# MercurialSDR_FPGA_P_P.net
KiCad netlist of a schematic drawn in Altium Designer
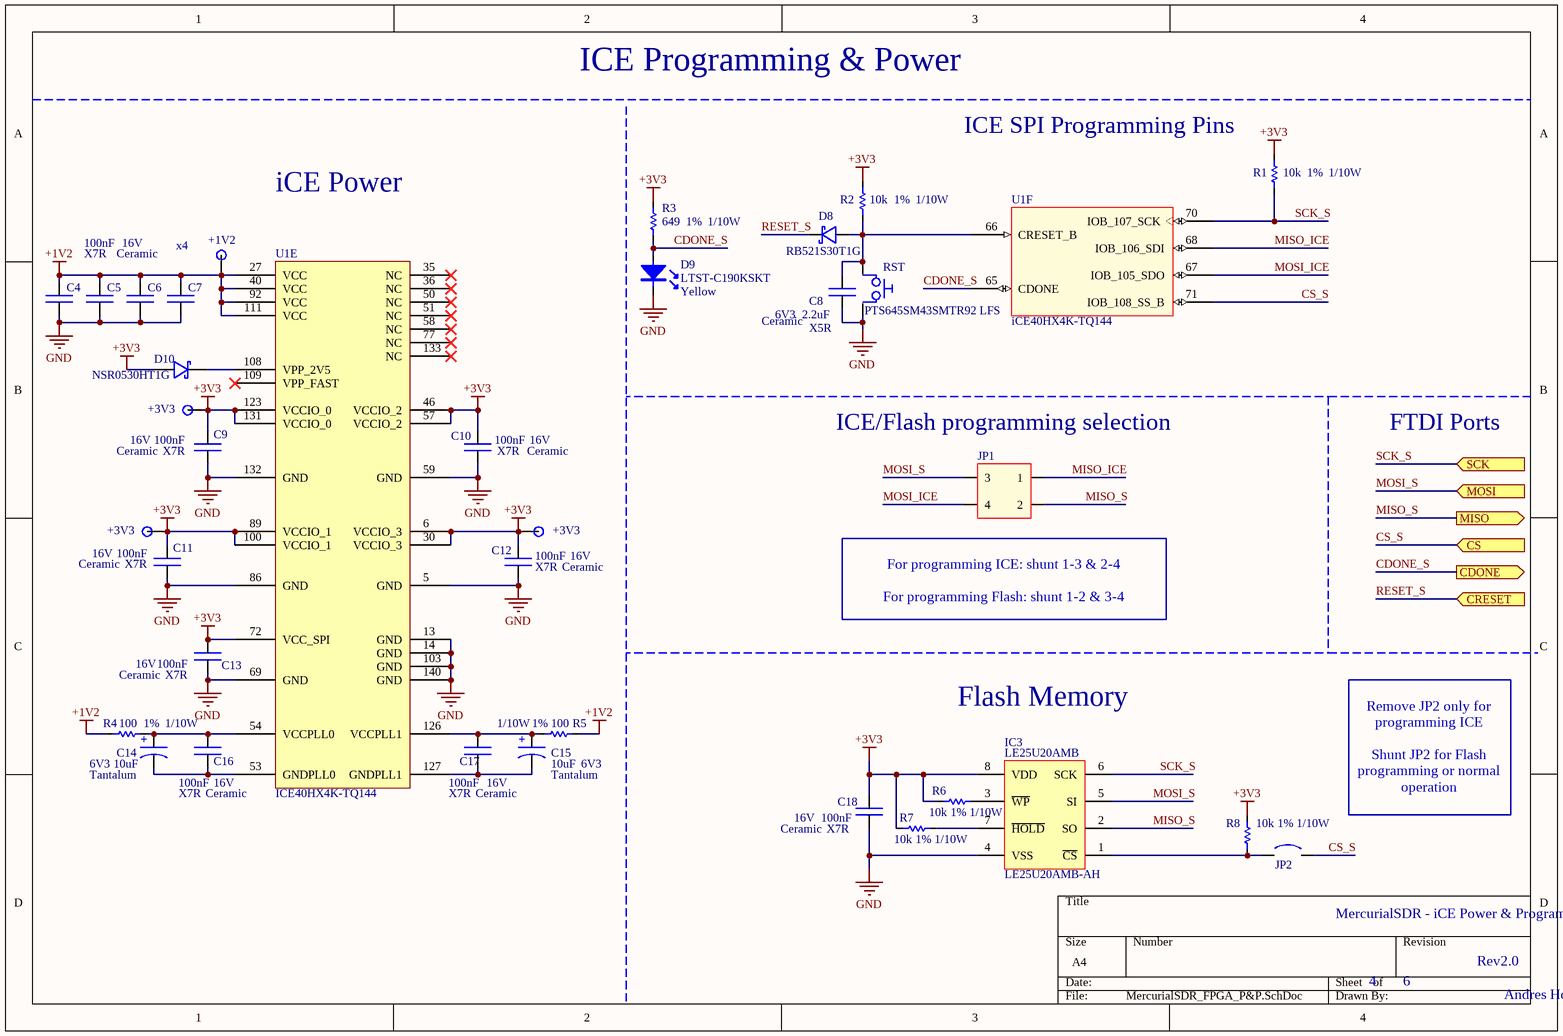
[diagram p0: MercurialSDR_FPGA_P&P.SchDoc]

(export (version "E")
  (design (tool "Eeschema 10.0.6"))
  (components
    (comp (ref "C4")
      (value "Capacitor")
      (footprint "CAP_0603")
      (description "Capacitor no polarizado")
      (fields (field (name "PART NUMBER") "CL10B104KO8NNNC"))
      (libsource (lib "MercurialSDR") (part "Cap"))
    )
    (comp (ref "C5")
      (value "Capacitor")
      (footprint "CAP_0603")
      (description "Capacitor no polarizado")
      (fields (field (name "PART NUMBER") "CL10B104KO8NNNC"))
      (libsource (lib "MercurialSDR") (part "Cap"))
    )
    (comp (ref "C6")
      (value "Capacitor")
      (footprint "CAP_0603")
      (description "Capacitor no polarizado")
      (fields (field (name "PART NUMBER") "CL10B104KO8NNNC"))
      (libsource (lib "MercurialSDR") (part "Cap"))
    )
    (comp (ref "C7")
      (value "100nF")
      (footprint "CAP_0603")
      (description "Capacitor no polarizado")
      (fields
        (field (name "TEMP COEF") "X7R")
        (field (name "PART NUMBER") "CL10B104KO8NNNC")
        (field (name "VR") "16V")
        (field (name "MATERIAL") "Ceramic")
        (field (name "Comment") "Capacitor")
      )
      (libsource (lib "MercurialSDR") (part "Cap"))
    )
    (comp (ref "C8")
      (value "2.2uF")
      (footprint "CAP_0603")
      (description "Capacitor no polarizado")
      (fields
        (field (name "TEMP COEF") "X5R")
        (field (name "PART NUMBER") "CL10A225KQ8NNNC")
        (field (name "VR") "6V3")
        (field (name "MATERIAL") "Ceramic")
        (field (name "Comment") "Capacitor")
      )
      (libsource (lib "MercurialSDR") (part "Cap"))
    )
    (comp (ref "C9")
      (value "100nF")
      (footprint "CAP_0603")
      (description "Capacitor no polarizado")
      (fields
        (field (name "TEMP COEF") "X7R")
        (field (name "PART NUMBER") "CL10B104KO8NNNC")
        (field (name "VR") "16V")
        (field (name "MATERIAL") "Ceramic")
        (field (name "Comment") "Capacitor")
      )
      (libsource (lib "MercurialSDR") (part "Cap"))
    )
    (comp (ref "C10")
      (value "100nF")
      (footprint "CAP_0603")
      (description "Capacitor no polarizado")
      (fields
        (field (name "TEMP COEF") "X7R")
        (field (name "PART NUMBER") "CL10B104KO8NNNC")
        (field (name "VR") "16V")
        (field (name "MATERIAL") "Ceramic")
        (field (name "Comment") "Capacitor")
      )
      (libsource (lib "MercurialSDR") (part "Cap"))
    )
    (comp (ref "C11")
      (value "100nF")
      (footprint "CAP_0603")
      (description "Capacitor no polarizado")
      (fields
        (field (name "TEMP COEF") "X7R")
        (field (name "PART NUMBER") "CL10B104KO8NNNC")
        (field (name "VR") "16V")
        (field (name "MATERIAL") "Ceramic")
        (field (name "Comment") "Capacitor")
      )
      (libsource (lib "MercurialSDR") (part "Cap"))
    )
    (comp (ref "C12")
      (value "100nF")
      (footprint "CAP_0603")
      (description "Capacitor no polarizado")
      (fields
        (field (name "TEMP COEF") "X7R")
        (field (name "PART NUMBER") "CL10B104KO8NNNC")
        (field (name "VR") "16V")
        (field (name "MATERIAL") "Ceramic")
        (field (name "Comment") "Capacitor")
      )
      (libsource (lib "MercurialSDR") (part "Cap"))
    )
    (comp (ref "C13")
      (value "100nF")
      (footprint "CAP_0603")
      (description "Capacitor no polarizado")
      (fields
        (field (name "TEMP COEF") "X7R")
        (field (name "PART NUMBER") "CL10B104KO8NNNC")
        (field (name "VR") "16V")
        (field (name "MATERIAL") "Ceramic")
        (field (name "Comment") "Capacitor")
      )
      (libsource (lib "MercurialSDR") (part "Cap"))
    )
    (comp (ref "C14")
      (value "10uF")
      (footprint "CAP_TANT_1206")
      (description "Capacitor polarizado")
      (fields
        (field (name "PART NUMBER") "TAJA106K006RNJ")
        (field (name "VR") "6V3")
        (field (name "MATERIAL") "Tantalum")
        (field (name "Comment") "Capacitor Polarizado")
      )
      (libsource (lib "MercurialSDR") (part "Cap Pol"))
    )
    (comp (ref "C15")
      (value "10uF")
      (footprint "CAP_TANT_1206")
      (description "Capacitor polarizado")
      (fields
        (field (name "PART NUMBER") "TAJA106K006RNJ")
        (field (name "VR") "6V3")
        (field (name "MATERIAL") "Tantalum")
        (field (name "Comment") "Capacitor Polarizado")
      )
      (libsource (lib "MercurialSDR") (part "Cap Pol"))
    )
    (comp (ref "C16")
      (value "100nF")
      (footprint "CAP_0603")
      (description "Capacitor no polarizado")
      (fields
        (field (name "TEMP COEF") "X7R")
        (field (name "PART NUMBER") "CL10B104KO8NNNC")
        (field (name "VR") "16V")
        (field (name "MATERIAL") "Ceramic")
        (field (name "Comment") "Capacitor")
      )
      (libsource (lib "MercurialSDR") (part "Cap"))
    )
    (comp (ref "C17")
      (value "100nF")
      (footprint "CAP_0603")
      (description "Capacitor no polarizado")
      (fields
        (field (name "TEMP COEF") "X7R")
        (field (name "PART NUMBER") "CL10B104KO8NNNC")
        (field (name "VR") "16V")
        (field (name "MATERIAL") "Ceramic")
        (field (name "Comment") "Capacitor")
      )
      (libsource (lib "MercurialSDR") (part "Cap"))
    )
    (comp (ref "C18")
      (value "100nF")
      (footprint "CAP_0603")
      (description "Capacitor no polarizado")
      (fields
        (field (name "TEMP COEF") "X7R")
        (field (name "PART NUMBER") "CL10B104KO8NNNC")
        (field (name "VR") "16V")
        (field (name "MATERIAL") "Ceramic")
        (field (name "Comment") "Capacitor")
      )
      (libsource (lib "MercurialSDR") (part "Cap"))
    )
    (comp (ref "D8")
      (value "Schottky Diode")
      (footprint "SOD-523")
      (description "Diodo Schottkey")
      (fields (field (name "PART NUMBER") "RB521S30T1G"))
      (libsource (lib "MercurialSDR") (part "Diodo_Schottky"))
    )
    (comp (ref "D9")
      (value "Led")
      (footprint "LED_0603")
      (fields (field (name "COLOR") "Yellow") (field (name "PART NUMBER") "LTST-C190KSKT"))
      (libsource (lib "MercurialSDR") (part "Led"))
    )
    (comp (ref "D10")
      (value "Schottky Diode")
      (footprint "SOD-323")
      (description "Diodo Schottkey")
      (fields (field (name "PART NUMBER") "NSR0530HT1G"))
      (libsource (lib "") (part "Diodo_Schottky_1"))
    )
    (comp (ref "IC3")
      (value "LE25U20AMB")
      (footprint "SOIC-8")
      (description "Flash Memmory SPI (256Kx8)")
      (fields (field (name "PART NUMBER") "LE25U20AMB-AH"))
      (libsource (lib "MercurialSDR") (part "LE25U20AMB"))
    )
    (comp (ref "JP1")
      (value "Jumper")
      (footprint "Jumper 2x2")
      (description "Jumper 2x2")
      (libsource (lib "MercurialSDR") (part "Jumper 2x2"))
    )
    (comp (ref "JP2")
      (value "Jumper")
      (footprint "Jumper 2x1")
      (libsource (lib "MercurialSDR") (part "Jumper"))
    )
    (comp (ref "R1")
      (value "10k")
      (footprint "RES_0603")
      (description "Resistor")
      (fields
        (field (name "POWER") "1/10W")
        (field (name "PART NUMBER") "CR0603-FX-1002EAS")
        (field (name "TOLERANCE") "1%")
        (field (name "Comment") "Resistor SMD")
      )
      (libsource (lib "MercurialSDR") (part "Res"))
    )
    (comp (ref "R2")
      (value "10k")
      (footprint "RES_0603")
      (description "Resistor")
      (fields
        (field (name "POWER") "1/10W")
        (field (name "PART NUMBER") "CR0603-FX-1002EAS")
        (field (name "TOLERANCE") "1%")
        (field (name "Comment") "Resistor SMD")
      )
      (libsource (lib "MercurialSDR") (part "Res"))
    )
    (comp (ref "R3")
      (value "649")
      (footprint "RES_0603")
      (description "Resistor")
      (fields
        (field (name "POWER") "1/10W")
        (field (name "PART NUMBER") "RC0603FR-07649RL")
        (field (name "TOLERANCE") "1%")
        (field (name "Comment") "Resistor SMD")
      )
      (libsource (lib "MercurialSDR") (part "Res"))
    )
    (comp (ref "R4")
      (value "100")
      (footprint "RES_0603")
      (description "Resistor")
      (fields
        (field (name "POWER") "1/10W")
        (field (name "PART NUMBER") "CR0603-FX-1000ELF")
        (field (name "TOLERANCE") "1%")
        (field (name "Comment") "Resistor SMD")
      )
      (libsource (lib "MercurialSDR") (part "Res"))
    )
    (comp (ref "R5")
      (value "100")
      (footprint "RES_0603")
      (description "Resistor")
      (fields
        (field (name "POWER") "1/10W")
        (field (name "PART NUMBER") "CR0603-FX-1000ELF")
        (field (name "TOLERANCE") "1%")
        (field (name "Comment") "Resistor SMD")
      )
      (libsource (lib "MercurialSDR") (part "Res"))
    )
    (comp (ref "R6")
      (value "10k")
      (footprint "RES_0603")
      (description "Resistor")
      (fields
        (field (name "POWER") "1/10W")
        (field (name "PART NUMBER") "CR0603-FX-1002EAS")
        (field (name "TOLERANCE") "1%")
        (field (name "Comment") "Resistor SMD")
      )
      (libsource (lib "MercurialSDR") (part "Res"))
    )
    (comp (ref "R7")
      (value "10k")
      (footprint "RES_0603")
      (description "Resistor")
      (fields
        (field (name "POWER") "1/10W")
        (field (name "PART NUMBER") "CR0603-FX-1002EAS")
        (field (name "TOLERANCE") "1%")
        (field (name "Comment") "Resistor SMD")
      )
      (libsource (lib "MercurialSDR") (part "Res"))
    )
    (comp (ref "R8")
      (value "10k")
      (footprint "RES_0603")
      (description "Resistor")
      (fields
        (field (name "POWER") "1/10W")
        (field (name "PART NUMBER") "CR0603-FX-1002EAS")
        (field (name "TOLERANCE") "1%")
        (field (name "Comment") "Resistor SMD")
      )
      (libsource (lib "MercurialSDR") (part "Res"))
    )
    (comp (ref "SW4")
      (value "Pulsador")
      (footprint "SWITCH_6X6mm")
      (fields (field (name "PART NUMBER") "PTS645SM43SMTR92 LFS") (field (name "SERIGRAFIA") "RST"))
      (libsource (lib "MercurialSDR") (part "Pulsador"))
    )
    (comp (ref "TP3")
      (value "Test Point")
      (footprint "TP_TOP")
      (fields (field (name "TP NAME") "+1V2"))
      (libsource (lib "MercurialSDR") (part "Test Point"))
    )
    (comp (ref "TP4")
      (value "Test Point")
      (footprint "TP_TOP")
      (fields (field (name "TP NAME") "+3V3"))
      (libsource (lib "MercurialSDR") (part "Test Point"))
    )
    (comp (ref "TP6")
      (value "Test Point")
      (footprint "TP_TOP")
      (fields (field (name "TP NAME") "+3V3"))
      (libsource (lib "MercurialSDR") (part "Test Point"))
    )
    (comp (ref "TP7")
      (value "Test Point")
      (footprint "TP_TOP")
      (fields (field (name "TP NAME") "+3V3"))
      (libsource (lib "MercurialSDR") (part "Test Point"))
    )
    (comp (ref "U1")
      (value "ICE40HX4K-TQ144")
      (footprint "LATC-TQFP-144_L")
      (fields
        (field (name "MANUFACTURER") "Lattice Semiconductor")
        (field (name "PARTNUMBER") "ICE40HX4K-TQ144")
      )
      (libsource (lib "MercurialSDR") (part "ICE40HX4K-TQ144"))
    )
  )
  (nets
    (net (code "1") (name "+1V2") (class "Default")
      (node (ref "C4") (pin "1") (pinfunction "1_1") (pintype "passive"))
      (node (ref "C5") (pin "1") (pinfunction "1_1") (pintype "passive"))
      (node (ref "C6") (pin "1") (pinfunction "1_1") (pintype "passive"))
      (node (ref "C7") (pin "1") (pinfunction "1_1") (pintype "passive"))
      (node (ref "R4") (pin "2") (pinfunction "2_2") (pintype "passive"))
      (node (ref "R5") (pin "1") (pinfunction "1_1") (pintype "passive"))
      (node (ref "TP3") (pin "1") (pinfunction "TP?_1") (pintype "passive"))
      (node (ref "U1") (pin "111") (pinfunction "VCC_111") (pintype "power_in"))
      (node (ref "U1") (pin "27") (pinfunction "VCC_27") (pintype "power_in"))
      (node (ref "U1") (pin "40") (pinfunction "VCC_40") (pintype "power_in"))
      (node (ref "U1") (pin "92") (pinfunction "VCC_92") (pintype "power_in"))
    )
    (net (code "2") (name "+3V3") (class "Default")
      (node (ref "C10") (pin "2") (pinfunction "2_2") (pintype "passive"))
      (node (ref "C11") (pin "2") (pinfunction "2_2") (pintype "passive"))
      (node (ref "C12") (pin "2") (pinfunction "2_2") (pintype "passive"))
      (node (ref "C13") (pin "2") (pinfunction "2_2") (pintype "passive"))
      (node (ref "C18") (pin "2") (pinfunction "2_2") (pintype "passive"))
      (node (ref "C9") (pin "2") (pinfunction "2_2") (pintype "passive"))
      (node (ref "D10") (pin "1") (pinfunction "A_1") (pintype "passive"))
      (node (ref "IC3") (pin "8") (pinfunction "VDD_8") (pintype "passive"))
      (node (ref "R1") (pin "1") (pinfunction "1_1") (pintype "passive"))
      (node (ref "R2") (pin "1") (pinfunction "1_1") (pintype "passive"))
      (node (ref "R3") (pin "1") (pinfunction "1_1") (pintype "passive"))
      (node (ref "R6") (pin "1") (pinfunction "1_1") (pintype "passive"))
      (node (ref "R7") (pin "1") (pinfunction "1_1") (pintype "passive"))
      (node (ref "R8") (pin "2") (pinfunction "2_2") (pintype "passive"))
      (node (ref "TP4") (pin "1") (pinfunction "TP?_1") (pintype "passive"))
      (node (ref "TP6") (pin "1") (pinfunction "TP?_1") (pintype "passive"))
      (node (ref "TP7") (pin "1") (pinfunction "TP?_1") (pintype "passive"))
      (node (ref "U1") (pin "100") (pinfunction "VCCIO_1_100") (pintype "power_in"))
      (node (ref "U1") (pin "123") (pinfunction "VCCIO_0_123") (pintype "power_in"))
      (node (ref "U1") (pin "131") (pinfunction "VCCIO_0_131") (pintype "power_in"))
      (node (ref "U1") (pin "30") (pinfunction "VCCIO_3_30") (pintype "power_in"))
      (node (ref "U1") (pin "46") (pinfunction "VCCIO_2_46") (pintype "power_in"))
      (node (ref "U1") (pin "57") (pinfunction "VCCIO_2_57") (pintype "power_in"))
      (node (ref "U1") (pin "6") (pinfunction "VCCIO_3_6") (pintype "power_in"))
      (node (ref "U1") (pin "72") (pinfunction "VCC_SPI_72") (pintype "power_in"))
      (node (ref "U1") (pin "89") (pinfunction "VCCIO_1_89") (pintype "power_in"))
    )
    (net (code "3") (name "/CDONE_S") (class "Default")
      (node (ref "D9") (pin "1") (pinfunction "A_1") (pintype "passive"))
      (node (ref "R3") (pin "2") (pinfunction "2_2") (pintype "passive"))
      (node (ref "U1") (pin "65") (pinfunction "CDONE_65") (pintype "bidirectional"))
    )
    (net (code "4") (name "/CS_S") (class "Default")
      (node (ref "JP2") (pin "2") (pinfunction "2_2") (pintype "passive"))
      (node (ref "U1") (pin "71") (pinfunction "IOB_108_SS_B_71") (pintype "bidirectional"))
    )
    (net (code "5") (name "/MISO_ICE") (class "Default")
      (node (ref "JP1") (pin "1") (pinfunction "1_1") (pintype "passive"))
      (node (ref "U1") (pin "68") (pinfunction "IOB_106_SDI_68") (pintype "bidirectional"))
    )
    (net (code "6") (name "/MISO_S") (class "Default")
      (node (ref "IC3") (pin "2") (pinfunction "SO_2") (pintype "passive"))
      (node (ref "JP1") (pin "2") (pinfunction "2_2") (pintype "passive"))
    )
    (net (code "7") (name "/MOSI_ICE") (class "Default")
      (node (ref "JP1") (pin "4") (pinfunction "4_4") (pintype "passive"))
      (node (ref "U1") (pin "67") (pinfunction "IOB_105_SDO_67") (pintype "bidirectional"))
    )
    (net (code "8") (name "/MOSI_S") (class "Default")
      (node (ref "IC3") (pin "5") (pinfunction "SI_5") (pintype "passive"))
      (node (ref "JP1") (pin "3") (pinfunction "3_3") (pintype "passive"))
    )
    (net (code "9") (name "/RESET_S") (class "Default")
      (node (ref "D8") (pin "2") (pinfunction "K_2") (pintype "passive"))
    )
    (net (code "10") (name "/SCK_S") (class "Default")
      (node (ref "IC3") (pin "6") (pinfunction "SCK_6") (pintype "passive"))
      (node (ref "R1") (pin "2") (pinfunction "2_2") (pintype "passive"))
      (node (ref "U1") (pin "70") (pinfunction "IOB_107_SCK_70") (pintype "bidirectional"))
    )
    (net (code "11") (name "GND") (class "Default")
      (node (ref "C10") (pin "1") (pinfunction "1_1") (pintype "passive"))
      (node (ref "C11") (pin "1") (pinfunction "1_1") (pintype "passive"))
      (node (ref "C12") (pin "1") (pinfunction "1_1") (pintype "passive"))
      (node (ref "C13") (pin "1") (pinfunction "1_1") (pintype "passive"))
      (node (ref "C18") (pin "1") (pinfunction "1_1") (pintype "passive"))
      (node (ref "C4") (pin "2") (pinfunction "2_2") (pintype "passive"))
      (node (ref "C5") (pin "2") (pinfunction "2_2") (pintype "passive"))
      (node (ref "C6") (pin "2") (pinfunction "2_2") (pintype "passive"))
      (node (ref "C7") (pin "2") (pinfunction "2_2") (pintype "passive"))
      (node (ref "C8") (pin "2") (pinfunction "2_2") (pintype "passive"))
      (node (ref "C9") (pin "1") (pinfunction "1_1") (pintype "passive"))
      (node (ref "D9") (pin "2") (pinfunction "K_2") (pintype "passive"))
      (node (ref "IC3") (pin "4") (pinfunction "VSS_4") (pintype "passive"))
      (node (ref "SW4") (pin "4") (pinfunction "4_4") (pintype "passive"))
      (node (ref "U1") (pin "103") (pinfunction "GND_103") (pintype "power_in"))
      (node (ref "U1") (pin "13") (pinfunction "GND_13") (pintype "power_in"))
      (node (ref "U1") (pin "132") (pinfunction "GND_132") (pintype "power_in"))
      (node (ref "U1") (pin "14") (pinfunction "GND_14") (pintype "power_in"))
      (node (ref "U1") (pin "140") (pinfunction "GND_140") (pintype "power_in"))
      (node (ref "U1") (pin "5") (pinfunction "GND_5") (pintype "power_in"))
      (node (ref "U1") (pin "59") (pinfunction "GND_59") (pintype "power_in"))
      (node (ref "U1") (pin "69") (pinfunction "GND_69") (pintype "power_in"))
      (node (ref "U1") (pin "86") (pinfunction "GND_86") (pintype "power_in"))
    )
    (net (code "12") (name "Net-(D8-A)") (class "Default")
      (node (ref "C8") (pin "1") (pinfunction "1_1") (pintype "passive"))
      (node (ref "D8") (pin "1") (pinfunction "A_1") (pintype "passive"))
      (node (ref "R2") (pin "2") (pinfunction "2_2") (pintype "passive"))
      (node (ref "SW4") (pin "1") (pinfunction "1_1") (pintype "passive"))
      (node (ref "U1") (pin "66") (pinfunction "CRESET_B_66") (pintype "input"))
    )
    (net (code "13") (name "Net-(D10-K)") (class "Default")
      (node (ref "D10") (pin "2") (pinfunction "K_2") (pintype "passive"))
      (node (ref "U1") (pin "108") (pinfunction "VPP_2V5_108") (pintype "power_in"))
    )
    (net (code "14") (name "Net-(IC3-~{CS})") (class "Default")
      (node (ref "IC3") (pin "1") (pinfunction "~{CS}_1") (pintype "passive"))
      (node (ref "JP2") (pin "1") (pinfunction "1_1") (pintype "passive"))
      (node (ref "R8") (pin "1") (pinfunction "1_1") (pintype "passive"))
    )
    (net (code "15") (name "Net-(IC3-~{HOLD})") (class "Default")
      (node (ref "IC3") (pin "7") (pinfunction "~{HOLD}_7") (pintype "passive"))
      (node (ref "R7") (pin "2") (pinfunction "2_2") (pintype "passive"))
    )
    (net (code "16") (name "Net-(IC3-~{WP})") (class "Default")
      (node (ref "IC3") (pin "3") (pinfunction "~{WP}_3") (pintype "passive"))
      (node (ref "R6") (pin "2") (pinfunction "2_2") (pintype "passive"))
    )
    (net (code "17") (name "Net-(U1E-GNDPLL0)") (class "Default")
      (node (ref "C14") (pin "2") (pinfunction "2_2") (pintype "passive"))
      (node (ref "C16") (pin "2") (pinfunction "2_2") (pintype "passive"))
      (node (ref "U1") (pin "53") (pinfunction "GNDPLL0_53") (pintype "power_in"))
    )
    (net (code "18") (name "Net-(U1E-GNDPLL1)") (class "Default")
      (node (ref "C15") (pin "2") (pinfunction "2_2") (pintype "passive"))
      (node (ref "C17") (pin "2") (pinfunction "2_2") (pintype "passive"))
      (node (ref "U1") (pin "127") (pinfunction "GNDPLL1_127") (pintype "power_in"))
    )
    (net (code "19") (name "Net-(U1E-VCCPLL0)") (class "Default")
      (node (ref "C14") (pin "1") (pinfunction "1_1") (pintype "passive"))
      (node (ref "C16") (pin "1") (pinfunction "1_1") (pintype "passive"))
      (node (ref "R4") (pin "1") (pinfunction "1_1") (pintype "passive"))
      (node (ref "U1") (pin "54") (pinfunction "VCCPLL0_54") (pintype "power_in"))
    )
    (net (code "20") (name "Net-(U1E-VCCPLL1)") (class "Default")
      (node (ref "C15") (pin "1") (pinfunction "1_1") (pintype "passive"))
      (node (ref "C17") (pin "1") (pinfunction "1_1") (pintype "passive"))
      (node (ref "R5") (pin "2") (pinfunction "2_2") (pintype "passive"))
      (node (ref "U1") (pin "126") (pinfunction "VCCPLL1_126") (pintype "power_in"))
    )
    (net (code "21") (name "unconnected-(SW4-Pad2)") (class "Default")
      (node (ref "SW4") (pin "2") (pinfunction "2_2") (pintype "passive"))
    )
    (net (code "22") (name "unconnected-(SW4-Pad3)") (class "Default")
      (node (ref "SW4") (pin "3") (pinfunction "3_3") (pintype "passive"))
    )
    (net (code "23") (name "unconnected-(U1E-NC-Pad35)") (class "Default")
      (node (ref "U1") (pin "35") (pinfunction "NC_35") (pintype "passive+no_connect"))
    )
    (net (code "24") (name "unconnected-(U1E-NC-Pad36)") (class "Default")
      (node (ref "U1") (pin "36") (pinfunction "NC_36") (pintype "passive+no_connect"))
    )
    (net (code "25") (name "unconnected-(U1E-NC-Pad50)") (class "Default")
      (node (ref "U1") (pin "50") (pinfunction "NC_50") (pintype "passive+no_connect"))
    )
    (net (code "26") (name "unconnected-(U1E-NC-Pad51)") (class "Default")
      (node (ref "U1") (pin "51") (pinfunction "NC_51") (pintype "passive+no_connect"))
    )
    (net (code "27") (name "unconnected-(U1E-NC-Pad58)") (class "Default")
      (node (ref "U1") (pin "58") (pinfunction "NC_58") (pintype "passive+no_connect"))
    )
    (net (code "28") (name "unconnected-(U1E-NC-Pad77)") (class "Default")
      (node (ref "U1") (pin "77") (pinfunction "NC_77") (pintype "passive+no_connect"))
    )
    (net (code "29") (name "unconnected-(U1E-NC-Pad133)") (class "Default")
      (node (ref "U1") (pin "133") (pinfunction "NC_133") (pintype "passive+no_connect"))
    )
    (net (code "30") (name "unconnected-(U1E-VPP_FAST-Pad109)") (class "Default")
      (node (ref "U1") (pin "109") (pinfunction "VPP_FAST_109") (pintype "power_in+no_connect"))
    )
  )
)
